# GRLV_double_Rail_v0_3_P1.net
KiCad netlist of a schematic drawn in Altium Designer
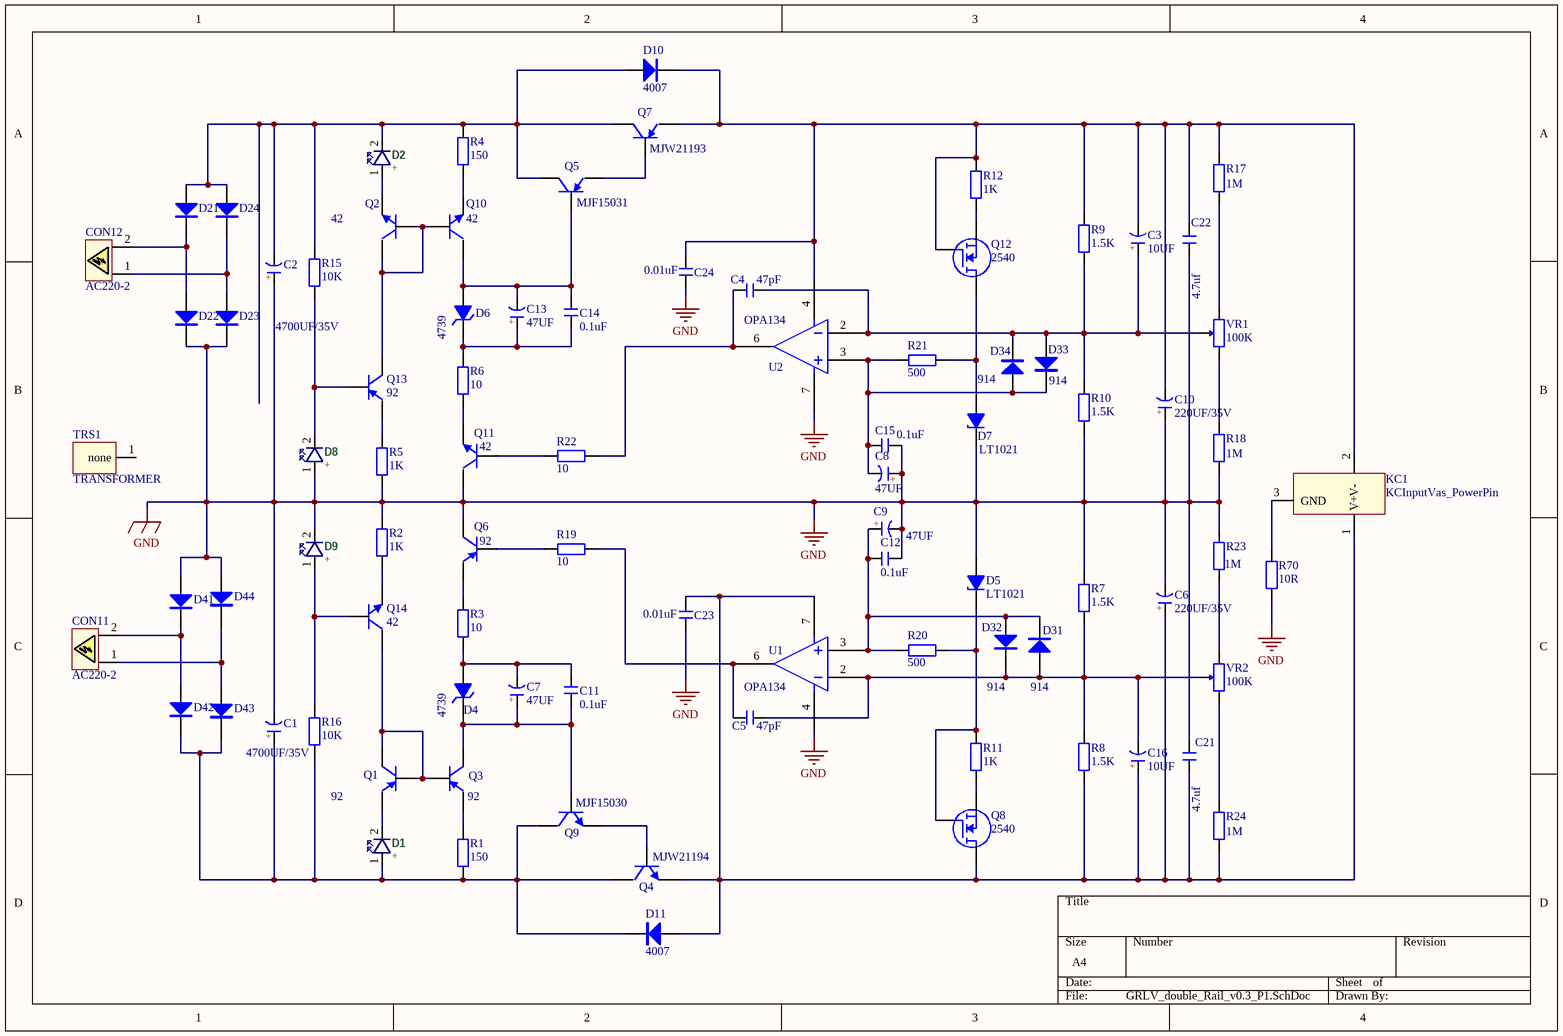
[diagram p0: GRLV_double_Rail_v0.3_P1.SchDoc]

(export (version "E")
  (design (tool "Eeschema 10.0.6"))
  (components
    (comp (ref "C1")
      (value "4700UF/35V")
      (footprint "CAP 10*22*31.5 - BK")
      (description "直插电解电容")
      (fields (field (name "版权归属") "源创客"))
      (libsource (lib "电阻-电容-电感") (part "C-CAP"))
    )
    (comp (ref "C2")
      (value "4700UF/35V")
      (footprint "CAP 10*22*31.5 - BK")
      (description "直插电解电容")
      (fields (field (name "版权归属") "源创客"))
      (libsource (lib "电阻-电容-电感") (part "C-CAP"))
    )
    (comp (ref "C3")
      (value "10UF")
      (footprint "CAP 2.5*6.3*7")
      (description "直插电解电容")
      (fields (field (name "版权归属") "源创客"))
      (libsource (lib "电阻-电容-电感") (part "C-CAP"))
    )
    (comp (ref "C4")
      (value "47pF")
      (footprint "CBB 6.3*6.3*5")
      (description "CBB电容")
      (fields (field (name "版权归属") "源创客"))
      (libsource (lib "电阻-电容-电感") (part "C-CBB"))
    )
    (comp (ref "C5")
      (value "47pF")
      (footprint "CBB 6.3*6.3*5")
      (description "CBB电容")
      (fields (field (name "版权归属") "源创客"))
      (libsource (lib "电阻-电容-电感") (part "C-CBB"))
    )
    (comp (ref "C6")
      (value "220UF/35V")
      (footprint "CAP 5.0*10*12.5")
      (description "直插电解电容")
      (fields (field (name "版权归属") "源创客"))
      (libsource (lib "电阻-电容-电感") (part "C-CAP"))
    )
    (comp (ref "C7")
      (value "47UF")
      (footprint "CAP 3.5*8*11.5")
      (description "直插电解电容")
      (fields (field (name "版权归属") "源创客"))
      (libsource (lib "电阻-电容-电感") (part "C-CAP"))
    )
    (comp (ref "C8")
      (value "47UF")
      (footprint "CAP 2.5*6.3*11.2")
      (description "直插电解电容")
      (fields (field (name "版权归属") "源创客"))
      (libsource (lib "") (part "C-CAP_1"))
    )
    (comp (ref "C9")
      (value "47UF")
      (footprint "CAP 2.5*6.3*11.2")
      (description "直插电解电容")
      (fields (field (name "版权归属") "源创客"))
      (libsource (lib "") (part "C-CAP_1"))
    )
    (comp (ref "C10")
      (value "220UF/35V")
      (footprint "CAP 5.0*10*12.5")
      (description "直插电解电容")
      (fields (field (name "版权归属") "源创客"))
      (libsource (lib "电阻-电容-电感") (part "C-CAP"))
    )
    (comp (ref "C11")
      (value "0.1uF")
      (footprint "CBB 6.3*6.3*5")
      (description "CBB电容")
      (fields (field (name "版权归属") "源创客"))
      (libsource (lib "电阻-电容-电感") (part "C-CBB"))
    )
    (comp (ref "C12")
      (value "0.1uF")
      (footprint "CBB 6.3*6.3*5")
      (description "CBB电容")
      (fields (field (name "版权归属") "源创客"))
      (libsource (lib "电阻-电容-电感") (part "C-CBB"))
    )
    (comp (ref "C13")
      (value "47UF")
      (footprint "CAP 3.5*8*11.5")
      (description "直插电解电容")
      (fields (field (name "版权归属") "源创客"))
      (libsource (lib "电阻-电容-电感") (part "C-CAP"))
    )
    (comp (ref "C14")
      (value "0.1uF")
      (footprint "CBB 6.3*6.3*5")
      (description "CBB电容")
      (fields (field (name "版权归属") "源创客"))
      (libsource (lib "电阻-电容-电感") (part "C-CBB"))
    )
    (comp (ref "C15")
      (value "0.1uF")
      (footprint "CBB 6.3*6.3*5")
      (description "CBB电容")
      (fields (field (name "版权归属") "源创客"))
      (libsource (lib "电阻-电容-电感") (part "C-CBB"))
    )
    (comp (ref "C16")
      (value "10UF")
      (footprint "CAP 2.5*6.3*7")
      (description "直插电解电容")
      (fields (field (name "版权归属") "源创客"))
      (libsource (lib "电阻-电容-电感") (part "C-CAP"))
    )
    (comp (ref "C21")
      (value "4.7uf")
      (footprint "CBB 7.2*7.2*13")
      (description "MKS薄膜电容")
      (libsource (lib "电阻-电容-电感") (part "C-MKS"))
    )
    (comp (ref "C22")
      (value "4.7uf")
      (footprint "CBB 7.2*7.2*13")
      (description "MKS薄膜电容")
      (libsource (lib "电阻-电容-电感") (part "C-MKS"))
    )
    (comp (ref "C23")
      (value "0.01uF")
      (footprint "CBB 6.3*6.3*5")
      (description "CBB电容")
      (fields (field (name "Comment") ".01") (field (name "版权归属") "源创客"))
      (libsource (lib "电阻-电容-电感") (part "C-CBB"))
    )
    (comp (ref "C24")
      (value "0.01uF")
      (footprint "CBB 6.3*6.3*5")
      (description "CBB电容")
      (fields (field (name "Comment") ".01") (field (name "版权归属") "源创客"))
      (libsource (lib "电阻-电容-电感") (part "C-CBB"))
    )
    (comp (ref "CON11")
      (value "AC220-2")
      (footprint "HX4.0-2XS")
      (libsource (lib "Connectors") (part "AC220-2"))
    )
    (comp (ref "CON12")
      (value "AC220-2")
      (footprint "HX4.0-2XS")
      (libsource (lib "Connectors") (part "AC220-2"))
    )
    (comp (ref "D1")
      (value "+")
      (footprint "LED 3MM-R")
      (description "直插式LED")
      (libsource (lib "LED") (part "LED"))
    )
    (comp (ref "D2")
      (value "+")
      (footprint "LED 3MM-R")
      (description "直插式LED")
      (libsource (lib "LED") (part "LED"))
    )
    (comp (ref "D4")
      (value "4739")
      (footprint "DO-41")
      (description "9.1V/1W稳压管")
      (libsource (lib "二极管-整流桥") (part "1N4739"))
    )
    (comp (ref "D5")
      (value "LT1021")
      (footprint "DIP8-300_MH")
      (description "10V Precision Reference 2 Pin Config")
      (libsource (lib "电压参考") (part "LT1021-10-2P"))
    )
    (comp (ref "D6")
      (value "4739")
      (footprint "DO-41")
      (description "9.1V/1W稳压管")
      (libsource (lib "二极管-整流桥") (part "1N4739"))
    )
    (comp (ref "D7")
      (value "LT1021")
      (footprint "DIP8-300_MH")
      (description "10V Precision Reference 2 Pin Config")
      (libsource (lib "电压参考") (part "LT1021-10-2P"))
    )
    (comp (ref "D8")
      (value "+")
      (footprint "LED 3MM-R")
      (description "直插式LED")
      (libsource (lib "LED") (part "LED"))
    )
    (comp (ref "D9")
      (value "+")
      (footprint "LED 3MM-R")
      (description "直插式LED")
      (libsource (lib "LED") (part "LED"))
    )
    (comp (ref "D10")
      (value "4007")
      (footprint "DO-41")
      (description "整流二极管")
      (fields (field (name "版权归属") "源创客"))
      (libsource (lib "二极管-整流桥") (part "1N4007"))
    )
    (comp (ref "D11")
      (value "4007")
      (footprint "DO-41")
      (description "整流二极管")
      (fields (field (name "版权归属") "源创客"))
      (libsource (lib "二极管-整流桥") (part "1N4007"))
    )
    (comp (ref "D21")
      (value "VS-HFA08TB60-M3")
      (footprint "DO-15XL")
      (description "Ultrafast Soft Recovery Diado 8A 600V")
      (libsource (lib "二极管-整流桥") (part "VS-HFA08TB60-M3"))
    )
    (comp (ref "D22")
      (value "VS-HFA08TB60-M3")
      (footprint "DO-15XL")
      (description "Ultrafast Soft Recovery Diado 8A 600V")
      (libsource (lib "二极管-整流桥") (part "VS-HFA08TB60-M3"))
    )
    (comp (ref "D23")
      (value "VS-HFA08TB60-M3")
      (footprint "DO-15XL")
      (description "Ultrafast Soft Recovery Diado 8A 600V")
      (libsource (lib "二极管-整流桥") (part "VS-HFA08TB60-M3"))
    )
    (comp (ref "D24")
      (value "VS-HFA08TB60-M3")
      (footprint "DO-15XL")
      (description "Ultrafast Soft Recovery Diado 8A 600V")
      (libsource (lib "二极管-整流桥") (part "VS-HFA08TB60-M3"))
    )
    (comp (ref "D31")
      (value "914")
      (footprint "DO-35")
      (description "高速开关管 1V/0.25W")
      (libsource (lib "二极管-整流桥") (part "1N914"))
    )
    (comp (ref "D32")
      (value "914")
      (footprint "DO-35")
      (description "高速开关管 1V/0.25W")
      (libsource (lib "二极管-整流桥") (part "1N914"))
    )
    (comp (ref "D33")
      (value "914")
      (footprint "DO-35")
      (description "高速开关管 1V/0.25W")
      (libsource (lib "二极管-整流桥") (part "1N914"))
    )
    (comp (ref "D34")
      (value "914")
      (footprint "DO-35")
      (description "高速开关管 1V/0.25W")
      (libsource (lib "二极管-整流桥") (part "1N914"))
    )
    (comp (ref "D41")
      (value "VS-HFA08TB60-M3")
      (footprint "DO-15XL")
      (description "Ultrafast Soft Recovery Diado 8A 600V")
      (libsource (lib "二极管-整流桥") (part "VS-HFA08TB60-M3"))
    )
    (comp (ref "D42")
      (value "VS-HFA08TB60-M3")
      (footprint "DO-15XL")
      (description "Ultrafast Soft Recovery Diado 8A 600V")
      (libsource (lib "二极管-整流桥") (part "VS-HFA08TB60-M3"))
    )
    (comp (ref "D43")
      (value "VS-HFA08TB60-M3")
      (footprint "DO-15XL")
      (description "Ultrafast Soft Recovery Diado 8A 600V")
      (libsource (lib "二极管-整流桥") (part "VS-HFA08TB60-M3"))
    )
    (comp (ref "D44")
      (value "VS-HFA08TB60-M3")
      (footprint "DO-15XL")
      (description "Ultrafast Soft Recovery Diado 8A 600V")
      (libsource (lib "二极管-整流桥") (part "VS-HFA08TB60-M3"))
    )
    (comp (ref "KC1")
      (value "KCInputVas_PowerPin")
      (footprint "KCIn_VAS_PowerPin_M2.0")
      (description "King Cello Input Stage and VAS")
      (libsource (lib "KC_amp") (part "KCInputVas_PowerPin"))
    )
    (comp (ref "Q1")
      (value "92")
      (footprint "TO92A")
      (description "High Voltage PNP Transistor")
      (libsource (lib "三极管") (part "KSP92/93"))
    )
    (comp (ref "Q2")
      (value "42")
      (footprint "TO92A")
      (description "High Voltage NPN Transistor")
      (libsource (lib "三极管") (part "KSP42/43"))
    )
    (comp (ref "Q3")
      (value "92")
      (footprint "TO92A")
      (description "High Voltage PNP Transistor")
      (libsource (lib "三极管") (part "KSP92/93"))
    )
    (comp (ref "Q4")
      (value "MJW21194")
      (footprint "TO247V")
      (description "Power NPN Transistor")
      (libsource (lib "三极管") (part "MJW21194"))
    )
    (comp (ref "Q5")
      (value "MJF15031")
      (footprint "TO220V")
      (description "Power PNP Transistor")
      (libsource (lib "三极管") (part "MJF15031"))
    )
    (comp (ref "Q6")
      (value "92")
      (footprint "TO92A")
      (description "High Voltage PNP Transistor")
      (libsource (lib "三极管") (part "KSP92/93"))
    )
    (comp (ref "Q7")
      (value "MJW21193")
      (footprint "TO247V")
      (description "Power PNP Transistor")
      (libsource (lib "三极管") (part "MJW21193"))
    )
    (comp (ref "Q8")
      (value "2540")
      (footprint "TO92A")
      (description "N沟道耗尽型DMOS场效应管 400V/150ma")
      (libsource (lib "场效应管") (part "DN2540"))
    )
    (comp (ref "Q9")
      (value "MJF15030")
      (footprint "TO220V")
      (description "Power NPN Transistor")
      (libsource (lib "三极管") (part "MJF15030"))
    )
    (comp (ref "Q10")
      (value "42")
      (footprint "TO92A")
      (description "High Voltage NPN Transistor")
      (libsource (lib "三极管") (part "KSP42/43"))
    )
    (comp (ref "Q11")
      (value "42")
      (footprint "TO92A")
      (description "High Voltage NPN Transistor")
      (libsource (lib "三极管") (part "KSP42/43"))
    )
    (comp (ref "Q12")
      (value "2540")
      (footprint "TO92A")
      (description "N沟道耗尽型DMOS场效应管 400V/150ma")
      (libsource (lib "场效应管") (part "DN2540"))
    )
    (comp (ref "Q13")
      (value "92")
      (footprint "TO92A")
      (description "High Voltage PNP Transistor")
      (libsource (lib "三极管") (part "KSP92/93"))
    )
    (comp (ref "Q14")
      (value "42")
      (footprint "TO92A")
      (description "High Voltage NPN Transistor")
      (libsource (lib "三极管") (part "KSP42/43"))
    )
    (comp (ref "R1")
      (value "150")
      (footprint "RS 1/4W")
      (description "直插色环电阻")
      (fields (field (name "版权归属") "源创客"))
      (libsource (lib "电阻-电容-电感") (part "R-CRR"))
    )
    (comp (ref "R2")
      (value "1K")
      (footprint "RS 1/4W")
      (description "直插色环电阻")
      (fields (field (name "版权归属") "源创客"))
      (libsource (lib "电阻-电容-电感") (part "R-CRR"))
    )
    (comp (ref "R3")
      (value "10")
      (footprint "RS 1/4W")
      (description "直插色环电阻")
      (fields (field (name "版权归属") "源创客"))
      (libsource (lib "电阻-电容-电感") (part "R-CRR"))
    )
    (comp (ref "R4")
      (value "150")
      (footprint "RS 1/4W")
      (description "直插色环电阻")
      (fields (field (name "版权归属") "源创客"))
      (libsource (lib "电阻-电容-电感") (part "R-CRR"))
    )
    (comp (ref "R5")
      (value "1K")
      (footprint "RS 1/4W")
      (description "直插色环电阻")
      (fields (field (name "版权归属") "源创客"))
      (libsource (lib "电阻-电容-电感") (part "R-CRR"))
    )
    (comp (ref "R6")
      (value "10")
      (footprint "RS 1/4W")
      (description "直插色环电阻")
      (fields (field (name "版权归属") "源创客"))
      (libsource (lib "电阻-电容-电感") (part "R-CRR"))
    )
    (comp (ref "R7")
      (value "1.5K")
      (footprint "RS 1/4W")
      (description "直插色环电阻")
      (fields (field (name "版权归属") "源创客"))
      (libsource (lib "电阻-电容-电感") (part "R-CRR"))
    )
    (comp (ref "R8")
      (value "1.5K")
      (footprint "RS 1/4W")
      (description "直插色环电阻")
      (fields (field (name "版权归属") "源创客"))
      (libsource (lib "电阻-电容-电感") (part "R-CRR"))
    )
    (comp (ref "R9")
      (value "1.5K")
      (footprint "RS 1/4W")
      (description "直插色环电阻")
      (fields (field (name "版权归属") "源创客"))
      (libsource (lib "电阻-电容-电感") (part "R-CRR"))
    )
    (comp (ref "R10")
      (value "1.5K")
      (footprint "RS 1/4W")
      (description "直插色环电阻")
      (fields (field (name "版权归属") "源创客"))
      (libsource (lib "电阻-电容-电感") (part "R-CRR"))
    )
    (comp (ref "R11")
      (value "1K")
      (footprint "RS 1/4W")
      (description "直插色环电阻")
      (fields (field (name "版权归属") "源创客"))
      (libsource (lib "电阻-电容-电感") (part "R-CRR"))
    )
    (comp (ref "R12")
      (value "1K")
      (footprint "RS 1/4W")
      (description "直插色环电阻")
      (fields (field (name "版权归属") "源创客"))
      (libsource (lib "电阻-电容-电感") (part "R-CRR"))
    )
    (comp (ref "R15")
      (value "10K")
      (footprint "RS 1/4W")
      (description "直插色环电阻")
      (fields (field (name "版权归属") "源创客"))
      (libsource (lib "电阻-电容-电感") (part "R-CRR"))
    )
    (comp (ref "R16")
      (value "10K")
      (footprint "RS 1/4W")
      (description "直插色环电阻")
      (fields (field (name "版权归属") "源创客"))
      (libsource (lib "电阻-电容-电感") (part "R-CRR"))
    )
    (comp (ref "R17")
      (value "1M")
      (footprint "RS 1/4W")
      (description "直插色环电阻")
      (fields (field (name "版权归属") "源创客"))
      (libsource (lib "电阻-电容-电感") (part "R-CRR"))
    )
    (comp (ref "R18")
      (value "1M")
      (footprint "RS 1/4W")
      (description "直插色环电阻")
      (fields (field (name "版权归属") "源创客"))
      (libsource (lib "电阻-电容-电感") (part "R-CRR"))
    )
    (comp (ref "R19")
      (value "10")
      (footprint "RS 1/4W")
      (description "直插色环电阻")
      (fields (field (name "版权归属") "源创客"))
      (libsource (lib "电阻-电容-电感") (part "R-CRR"))
    )
    (comp (ref "R20")
      (value "500")
      (footprint "RS 1/4W")
      (description "直插色环电阻")
      (fields (field (name "版权归属") "源创客"))
      (libsource (lib "电阻-电容-电感") (part "R-CRR"))
    )
    (comp (ref "R21")
      (value "500")
      (footprint "RS 1/4W")
      (description "直插色环电阻")
      (fields (field (name "版权归属") "源创客"))
      (libsource (lib "电阻-电容-电感") (part "R-CRR"))
    )
    (comp (ref "R22")
      (value "10")
      (footprint "RS 1/4W")
      (description "直插色环电阻")
      (fields (field (name "版权归属") "源创客"))
      (libsource (lib "电阻-电容-电感") (part "R-CRR"))
    )
    (comp (ref "R23")
      (value "1M")
      (footprint "RS 1/4W")
      (description "直插色环电阻")
      (fields (field (name "版权归属") "源创客"))
      (libsource (lib "电阻-电容-电感") (part "R-CRR"))
    )
    (comp (ref "R24")
      (value "1M")
      (footprint "RS 1/4W")
      (description "直插色环电阻")
      (fields (field (name "版权归属") "源创客"))
      (libsource (lib "电阻-电容-电感") (part "R-CRR"))
    )
    (comp (ref "R70")
      (value "10R")
      (footprint "RS 1/2W")
      (description "直插色环电阻")
      (fields (field (name "版权归属") "源创客"))
      (libsource (lib "电阻-电容-电感") (part "R-CRR"))
    )
    (comp (ref "TRS1")
      (value "TRANSFORMER")
      (footprint "TRANS_BLOCK_m4_68mm")
      (description "Transformer")
      (libsource (lib "KC_amp") (part "TRANSFORMER"))
    )
    (comp (ref "U1") (value "OPA134") (footprint "DIP8-300_MH") (libsource (lib "运放") (part "OPA134PA")))
    (comp (ref "U2") (value "OPA134") (footprint "DIP8-300_MH") (libsource (lib "运放") (part "OPA134PA")))
    (comp (ref "VR1")
      (value "100K")
      (footprint "RS 1/2W-VR")
      (description "直插可调电阻-顶调")
      (libsource (lib "电阻-电容-电感") (part "VR-W"))
    )
    (comp (ref "VR2")
      (value "100K")
      (footprint "RS 1/2W-VR")
      (description "直插可调电阻-顶调")
      (libsource (lib "电阻-电容-电感") (part "VR-W"))
    )
  )
  (nets
    (net (code "1") (name "GND") (class "Default")
      (node (ref "C1") (pin "2") (pinfunction "K_2") (pintype "passive"))
      (node (ref "C10") (pin "1") (pinfunction "A_1") (pintype "passive"))
      (node (ref "C12") (pin "2") (pinfunction "2_2") (pintype "passive"))
      (node (ref "C15") (pin "2") (pinfunction "2_2") (pintype "passive"))
      (node (ref "C2") (pin "1") (pinfunction "A_1") (pintype "passive"))
      (node (ref "C21") (pin "2") (pinfunction "2_2") (pintype "passive"))
      (node (ref "C22") (pin "1") (pinfunction "1_1") (pintype "passive"))
      (node (ref "C23") (pin "1") (pinfunction "1_1") (pintype "passive"))
      (node (ref "C24") (pin "1") (pinfunction "1_1") (pintype "passive"))
      (node (ref "C6") (pin "2") (pinfunction "K_2") (pintype "passive"))
      (node (ref "C8") (pin "1") (pinfunction "A_1") (pintype "passive"))
      (node (ref "C9") (pin "2") (pinfunction "K_2") (pintype "passive"))
      (node (ref "D22") (pin "1") (pinfunction "Cathode_1") (pintype "passive"))
      (node (ref "D23") (pin "1") (pinfunction "Cathode_1") (pintype "passive"))
      (node (ref "D41") (pin "2") (pinfunction "Anode_2") (pintype "passive"))
      (node (ref "D44") (pin "2") (pinfunction "Anode_2") (pintype "passive"))
      (node (ref "D5") (pin "4") (pinfunction "A_4") (pintype "passive"))
      (node (ref "D7") (pin "6") (pinfunction "K_6") (pintype "passive"))
      (node (ref "D8") (pin "1") (pinfunction "A_1") (pintype "passive"))
      (node (ref "D9") (pin "2") (pinfunction "K_2") (pintype "passive"))
      (node (ref "Q11") (pin "3") (pinfunction "C_3") (pintype "passive"))
      (node (ref "Q6") (pin "3") (pinfunction "C_3") (pintype "passive"))
      (node (ref "R10") (pin "1") (pinfunction "1_1") (pintype "passive"))
      (node (ref "R18") (pin "1") (pinfunction "1_1") (pintype "passive"))
      (node (ref "R2") (pin "2") (pinfunction "2_2") (pintype "passive"))
      (node (ref "R23") (pin "2") (pinfunction "2_2") (pintype "passive"))
      (node (ref "R5") (pin "1") (pinfunction "1_1") (pintype "passive"))
      (node (ref "R7") (pin "2") (pinfunction "2_2") (pintype "passive"))
      (node (ref "R70") (pin "1") (pinfunction "1_1") (pintype "passive"))
      (node (ref "U1") (pin "4") (pinfunction "V-_4") (pintype "passive"))
      (node (ref "U2") (pin "7") (pinfunction "V+_7") (pintype "passive"))
    )
    (net (code "2") (name "Net-(C1-A)") (class "Default")
      (node (ref "C1") (pin "1") (pinfunction "A_1") (pintype "passive"))
      (node (ref "D1") (pin "1") (pinfunction "A_1") (pintype "passive"))
      (node (ref "D11") (pin "2") (pinfunction "K_2") (pintype "passive"))
      (node (ref "D42") (pin "1") (pinfunction "Cathode_1") (pintype "passive"))
      (node (ref "D43") (pin "1") (pinfunction "Cathode_1") (pintype "passive"))
      (node (ref "Q4") (pin "2") (pinfunction "C_2") (pintype "passive"))
      (node (ref "Q9") (pin "2") (pinfunction "C_2") (pintype "passive"))
      (node (ref "R1") (pin "1") (pinfunction "1_1") (pintype "passive"))
      (node (ref "R16") (pin "1") (pinfunction "1_1") (pintype "passive"))
    )
    (net (code "3") (name "Net-(C2-K)") (class "Default")
      (node (ref "C2") (pin "2") (pinfunction "K_2") (pintype "passive"))
      (node (ref "D10") (pin "1") (pinfunction "A_1") (pintype "passive"))
      (node (ref "D2") (pin "2") (pinfunction "K_2") (pintype "passive"))
      (node (ref "D21") (pin "2") (pinfunction "Anode_2") (pintype "passive"))
      (node (ref "D24") (pin "2") (pinfunction "Anode_2") (pintype "passive"))
      (node (ref "Q5") (pin "2") (pinfunction "C_2") (pintype "passive"))
      (node (ref "Q7") (pin "2") (pinfunction "C_2") (pintype "passive"))
      (node (ref "R15") (pin "2") (pinfunction "2_2") (pintype "passive"))
      (node (ref "R4") (pin "2") (pinfunction "2_2") (pintype "passive"))
    )
    (net (code "4") (name "Net-(C3-A)") (class "Default")
      (node (ref "C3") (pin "1") (pinfunction "A_1") (pintype "passive"))
      (node (ref "C4") (pin "2") (pinfunction "2_2") (pintype "passive"))
      (node (ref "D33") (pin "1") (pinfunction "A_1") (pintype "passive"))
      (node (ref "D34") (pin "2") (pinfunction "K_2") (pintype "passive"))
      (node (ref "R10") (pin "2") (pinfunction "2_2") (pintype "passive"))
      (node (ref "R9") (pin "1") (pinfunction "1_1") (pintype "passive"))
      (node (ref "U2") (pin "2") (pinfunction "-in_2") (pintype "passive"))
      (node (ref "VR1") (pin "3") (pinfunction "3_3") (pintype "passive"))
    )
    (net (code "5") (name "Net-(C7-A)") (class "Default")
      (node (ref "C11") (pin "1") (pinfunction "1_1") (pintype "passive"))
      (node (ref "C7") (pin "1") (pinfunction "A_1") (pintype "passive"))
      (node (ref "D4") (pin "2") (pinfunction "K_2") (pintype "passive"))
      (node (ref "Q3") (pin "3") (pinfunction "C_3") (pintype "passive"))
      (node (ref "Q9") (pin "1") (pinfunction "B_1") (pintype "passive"))
    )
    (net (code "6") (name "Net-(C7-K)") (class "Default")
      (node (ref "C11") (pin "2") (pinfunction "2_2") (pintype "passive"))
      (node (ref "C7") (pin "2") (pinfunction "K_2") (pintype "passive"))
      (node (ref "D4") (pin "1") (pinfunction "A_1") (pintype "passive"))
      (node (ref "R3") (pin "1") (pinfunction "1_1") (pintype "passive"))
    )
    (net (code "7") (name "Net-(C8-K)") (class "Default")
      (node (ref "C15") (pin "1") (pinfunction "1_1") (pintype "passive"))
      (node (ref "C8") (pin "2") (pinfunction "K_2") (pintype "passive"))
      (node (ref "D33") (pin "2") (pinfunction "K_2") (pintype "passive"))
      (node (ref "D34") (pin "1") (pinfunction "A_1") (pintype "passive"))
      (node (ref "R21") (pin "1") (pinfunction "1_1") (pintype "passive"))
      (node (ref "U2") (pin "3") (pinfunction "+in_3") (pintype "passive"))
    )
    (net (code "8") (name "Net-(C9-A)") (class "Default")
      (node (ref "C12") (pin "1") (pinfunction "1_1") (pintype "passive"))
      (node (ref "C9") (pin "1") (pinfunction "A_1") (pintype "passive"))
      (node (ref "D31") (pin "2") (pinfunction "K_2") (pintype "passive"))
      (node (ref "D32") (pin "1") (pinfunction "A_1") (pintype "passive"))
      (node (ref "R20") (pin "1") (pinfunction "1_1") (pintype "passive"))
      (node (ref "U1") (pin "3") (pinfunction "+in_3") (pintype "passive"))
    )
    (net (code "9") (name "Net-(C10-K)") (class "Default")
      (node (ref "C10") (pin "2") (pinfunction "K_2") (pintype "passive"))
      (node (ref "C22") (pin "2") (pinfunction "2_2") (pintype "passive"))
      (node (ref "C24") (pin "2") (pinfunction "2_2") (pintype "passive"))
      (node (ref "C3") (pin "2") (pinfunction "K_2") (pintype "passive"))
      (node (ref "D10") (pin "2") (pinfunction "K_2") (pintype "passive"))
      (node (ref "KC1") (pin "2") (pinfunction "V-_2") (pintype "passive"))
      (node (ref "Q12") (pin "2") (pinfunction "G_2") (pintype "passive"))
      (node (ref "Q7") (pin "3") (pinfunction "E_3") (pintype "passive"))
      (node (ref "R12") (pin "2") (pinfunction "2_2") (pintype "passive"))
      (node (ref "R17") (pin "2") (pinfunction "2_2") (pintype "passive"))
      (node (ref "R9") (pin "2") (pinfunction "2_2") (pintype "passive"))
      (node (ref "U2") (pin "4") (pinfunction "V-_4") (pintype "passive"))
    )
    (net (code "10") (name "Net-(C13-A)") (class "Default")
      (node (ref "C13") (pin "1") (pinfunction "A_1") (pintype "passive"))
      (node (ref "C14") (pin "1") (pinfunction "1_1") (pintype "passive"))
      (node (ref "D6") (pin "2") (pinfunction "K_2") (pintype "passive"))
      (node (ref "R6") (pin "2") (pinfunction "2_2") (pintype "passive"))
    )
    (net (code "11") (name "Net-(C13-K)") (class "Default")
      (node (ref "C13") (pin "2") (pinfunction "K_2") (pintype "passive"))
      (node (ref "C14") (pin "2") (pinfunction "2_2") (pintype "passive"))
      (node (ref "D6") (pin "1") (pinfunction "A_1") (pintype "passive"))
      (node (ref "Q10") (pin "3") (pinfunction "C_3") (pintype "passive"))
      (node (ref "Q5") (pin "1") (pinfunction "B_1") (pintype "passive"))
    )
    (net (code "12") (name "Net-(C16-A)") (class "Default")
      (node (ref "C16") (pin "1") (pinfunction "A_1") (pintype "passive"))
      (node (ref "C21") (pin "1") (pinfunction "1_1") (pintype "passive"))
      (node (ref "C23") (pin "2") (pinfunction "2_2") (pintype "passive"))
      (node (ref "C6") (pin "1") (pinfunction "A_1") (pintype "passive"))
      (node (ref "D11") (pin "1") (pinfunction "A_1") (pintype "passive"))
      (node (ref "KC1") (pin "1") (pinfunction "V+_1") (pintype "passive"))
      (node (ref "Q4") (pin "3") (pinfunction "E_3") (pintype "passive"))
      (node (ref "Q8") (pin "3") (pinfunction "D_3") (pintype "passive"))
      (node (ref "R24") (pin "1") (pinfunction "1_1") (pintype "passive"))
      (node (ref "R8") (pin "1") (pinfunction "1_1") (pintype "passive"))
      (node (ref "U1") (pin "7") (pinfunction "V+_7") (pintype "passive"))
    )
    (net (code "13") (name "Net-(C16-K)") (class "Default")
      (node (ref "C16") (pin "2") (pinfunction "K_2") (pintype "passive"))
      (node (ref "C5") (pin "2") (pinfunction "2_2") (pintype "passive"))
      (node (ref "D31") (pin "1") (pinfunction "A_1") (pintype "passive"))
      (node (ref "D32") (pin "2") (pinfunction "K_2") (pintype "passive"))
      (node (ref "R7") (pin "1") (pinfunction "1_1") (pintype "passive"))
      (node (ref "R8") (pin "2") (pinfunction "2_2") (pintype "passive"))
      (node (ref "U1") (pin "2") (pinfunction "-in_2") (pintype "passive"))
      (node (ref "VR2") (pin "3") (pinfunction "3_3") (pintype "passive"))
    )
    (net (code "14") (name "Net-(CON11-G)") (class "Default")
      (node (ref "CON11") (pin "2") (pinfunction "G_2") (pintype "passive"))
      (node (ref "D41") (pin "1") (pinfunction "Cathode_1") (pintype "passive"))
      (node (ref "D42") (pin "2") (pinfunction "Anode_2") (pintype "passive"))
    )
    (net (code "15") (name "Net-(CON11-L)") (class "Default")
      (node (ref "CON11") (pin "1") (pinfunction "L_1") (pintype "passive"))
      (node (ref "D43") (pin "2") (pinfunction "Anode_2") (pintype "passive"))
      (node (ref "D44") (pin "1") (pinfunction "Cathode_1") (pintype "passive"))
    )
    (net (code "16") (name "Net-(CON12-G)") (class "Default")
      (node (ref "CON12") (pin "2") (pinfunction "G_2") (pintype "passive"))
      (node (ref "D21") (pin "1") (pinfunction "Cathode_1") (pintype "passive"))
      (node (ref "D22") (pin "2") (pinfunction "Anode_2") (pintype "passive"))
    )
    (net (code "17") (name "Net-(CON12-L)") (class "Default")
      (node (ref "CON12") (pin "1") (pinfunction "L_1") (pintype "passive"))
      (node (ref "D23") (pin "2") (pinfunction "Anode_2") (pintype "passive"))
      (node (ref "D24") (pin "1") (pinfunction "Cathode_1") (pintype "passive"))
    )
    (net (code "18") (name "Net-(D1-K)") (class "Default")
      (node (ref "D1") (pin "2") (pinfunction "K_2") (pintype "passive"))
      (node (ref "Q1") (pin "1") (pinfunction "E_1") (pintype "passive"))
    )
    (net (code "19") (name "Net-(D2-A)") (class "Default")
      (node (ref "D2") (pin "1") (pinfunction "A_1") (pintype "passive"))
      (node (ref "Q2") (pin "1") (pinfunction "E_1") (pintype "passive"))
    )
    (net (code "20") (name "Net-(D5-K)") (class "Default")
      (node (ref "D5") (pin "6") (pinfunction "K_6") (pintype "passive"))
      (node (ref "Q8") (pin "2") (pinfunction "G_2") (pintype "passive"))
      (node (ref "R11") (pin "2") (pinfunction "2_2") (pintype "passive"))
      (node (ref "R20") (pin "2") (pinfunction "2_2") (pintype "passive"))
    )
    (net (code "21") (name "Net-(D7-A)") (class "Default")
      (node (ref "D7") (pin "4") (pinfunction "A_4") (pintype "passive"))
      (node (ref "Q12") (pin "3") (pinfunction "D_3") (pintype "passive"))
      (node (ref "R21") (pin "2") (pinfunction "2_2") (pintype "passive"))
    )
    (net (code "22") (name "Net-(D8-K)") (class "Default")
      (node (ref "D8") (pin "2") (pinfunction "K_2") (pintype "passive"))
      (node (ref "Q13") (pin "2") (pinfunction "B_2") (pintype "passive"))
      (node (ref "R15") (pin "1") (pinfunction "1_1") (pintype "passive"))
    )
    (net (code "23") (name "Net-(D9-A)") (class "Default")
      (node (ref "D9") (pin "1") (pinfunction "A_1") (pintype "passive"))
      (node (ref "Q14") (pin "2") (pinfunction "B_2") (pintype "passive"))
      (node (ref "R16") (pin "2") (pinfunction "2_2") (pintype "passive"))
    )
    (net (code "24") (name "Net-(KC1-GND)") (class "Default")
      (node (ref "KC1") (pin "3") (pinfunction "GND_3") (pintype "passive"))
      (node (ref "R70") (pin "2") (pinfunction "2_2") (pintype "passive"))
    )
    (net (code "25") (name "Net-(Q1-B)") (class "Default")
      (node (ref "Q1") (pin "2") (pinfunction "B_2") (pintype "passive"))
      (node (ref "Q1") (pin "3") (pinfunction "C_3") (pintype "passive"))
      (node (ref "Q14") (pin "3") (pinfunction "C_3") (pintype "passive"))
      (node (ref "Q3") (pin "2") (pinfunction "B_2") (pintype "passive"))
    )
    (net (code "26") (name "Net-(Q3-E)") (class "Default")
      (node (ref "Q3") (pin "1") (pinfunction "E_1") (pintype "passive"))
      (node (ref "R1") (pin "2") (pinfunction "2_2") (pintype "passive"))
    )
    (net (code "27") (name "Net-(Q4-B)") (class "Default")
      (node (ref "Q4") (pin "1") (pinfunction "B_1") (pintype "passive"))
      (node (ref "Q9") (pin "3") (pinfunction "E_3") (pintype "passive"))
    )
    (net (code "28") (name "Net-(Q5-E)") (class "Default")
      (node (ref "Q5") (pin "3") (pinfunction "E_3") (pintype "passive"))
      (node (ref "Q7") (pin "1") (pinfunction "B_1") (pintype "passive"))
    )
    (net (code "29") (name "Net-(Q6-B)") (class "Default")
      (node (ref "Q6") (pin "2") (pinfunction "B_2") (pintype "passive"))
      (node (ref "R19") (pin "1") (pinfunction "1_1") (pintype "passive"))
    )
    (net (code "30") (name "Net-(Q6-E)") (class "Default")
      (node (ref "Q6") (pin "1") (pinfunction "E_1") (pintype "passive"))
      (node (ref "R3") (pin "2") (pinfunction "2_2") (pintype "passive"))
    )
    (net (code "31") (name "Net-(Q8-S)") (class "Default")
      (node (ref "Q8") (pin "1") (pinfunction "S_1") (pintype "passive"))
      (node (ref "R11") (pin "1") (pinfunction "1_1") (pintype "passive"))
    )
    (net (code "32") (name "Net-(Q10-B)") (class "Default")
      (node (ref "Q10") (pin "2") (pinfunction "B_2") (pintype "passive"))
      (node (ref "Q13") (pin "3") (pinfunction "C_3") (pintype "passive"))
      (node (ref "Q2") (pin "2") (pinfunction "B_2") (pintype "passive"))
      (node (ref "Q2") (pin "3") (pinfunction "C_3") (pintype "passive"))
    )
    (net (code "33") (name "Net-(Q10-E)") (class "Default")
      (node (ref "Q10") (pin "1") (pinfunction "E_1") (pintype "passive"))
      (node (ref "R4") (pin "1") (pinfunction "1_1") (pintype "passive"))
    )
    (net (code "34") (name "Net-(Q11-B)") (class "Default")
      (node (ref "Q11") (pin "2") (pinfunction "B_2") (pintype "passive"))
      (node (ref "R22") (pin "1") (pinfunction "1_1") (pintype "passive"))
    )
    (net (code "35") (name "Net-(Q11-E)") (class "Default")
      (node (ref "Q11") (pin "1") (pinfunction "E_1") (pintype "passive"))
      (node (ref "R6") (pin "1") (pinfunction "1_1") (pintype "passive"))
    )
    (net (code "36") (name "Net-(Q12-S)") (class "Default")
      (node (ref "Q12") (pin "1") (pinfunction "S_1") (pintype "passive"))
      (node (ref "R12") (pin "1") (pinfunction "1_1") (pintype "passive"))
    )
    (net (code "37") (name "Net-(Q13-E)") (class "Default")
      (node (ref "Q13") (pin "1") (pinfunction "E_1") (pintype "passive"))
      (node (ref "R5") (pin "2") (pinfunction "2_2") (pintype "passive"))
    )
    (net (code "38") (name "Net-(Q14-E)") (class "Default")
      (node (ref "Q14") (pin "1") (pinfunction "E_1") (pintype "passive"))
      (node (ref "R2") (pin "1") (pinfunction "1_1") (pintype "passive"))
    )
    (net (code "39") (name "Net-(R17-Pad1)") (class "Default")
      (node (ref "R17") (pin "1") (pinfunction "1_1") (pintype "passive"))
      (node (ref "VR1") (pin "2") (pinfunction "2_2") (pintype "passive"))
    )
    (net (code "40") (name "Net-(R18-Pad2)") (class "Default")
      (node (ref "R18") (pin "2") (pinfunction "2_2") (pintype "passive"))
      (node (ref "VR1") (pin "1") (pinfunction "1_1") (pintype "passive"))
    )
    (net (code "41") (name "Net-(R23-Pad1)") (class "Default")
      (node (ref "R23") (pin "1") (pinfunction "1_1") (pintype "passive"))
      (node (ref "VR2") (pin "2") (pinfunction "2_2") (pintype "passive"))
    )
    (net (code "42") (name "Net-(R24-Pad2)") (class "Default")
      (node (ref "R24") (pin "2") (pinfunction "2_2") (pintype "passive"))
      (node (ref "VR2") (pin "1") (pinfunction "1_1") (pintype "passive"))
    )
    (net (code "43") (name "Net-(U1-out)") (class "Default")
      (node (ref "C5") (pin "1") (pinfunction "1_1") (pintype "passive"))
      (node (ref "R19") (pin "2") (pinfunction "2_2") (pintype "passive"))
      (node (ref "U1") (pin "6") (pinfunction "out_6") (pintype "passive"))
    )
    (net (code "44") (name "Net-(U2-out)") (class "Default")
      (node (ref "C4") (pin "1") (pinfunction "1_1") (pintype "passive"))
      (node (ref "R22") (pin "2") (pinfunction "2_2") (pintype "passive"))
      (node (ref "U2") (pin "6") (pinfunction "out_6") (pintype "passive"))
    )
    (net (code "45") (name "unconnected-(TRS1-none-Pad1)") (class "Default")
      (node (ref "TRS1") (pin "1") (pinfunction "none_1") (pintype "passive"))
    )
  )
)
